# Bluetooth.net
KiCad netlist of a schematic drawn in Altium Designer
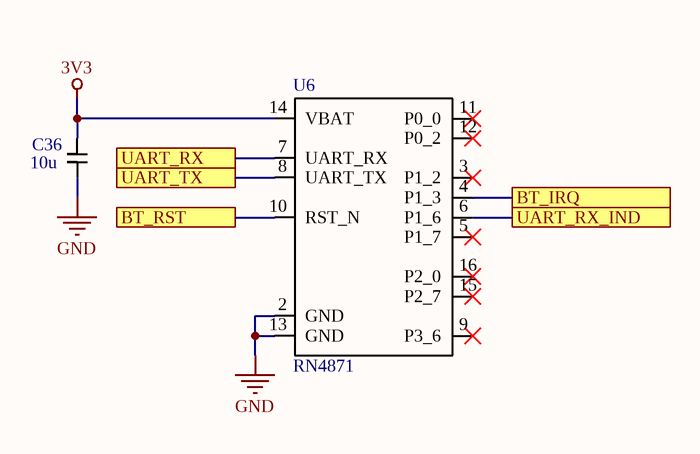
[diagram p0: Bluetooth.SchDoc]

(export (version "E")
  (design (tool "Eeschema 10.0.6"))
  (components
    (comp (ref "C36")
      (value "10u")
      (footprint "Capacitor_0603")
      (libsource (lib "NautilusKB") (part "Capacitor"))
    )
    (comp (ref "U6") (value "RN4871") (footprint "RN4871") (libsource (lib "NautilusKB") (part "RN4871")))
  )
  (nets
    (net (code "1") (name "/BT_IRQ") (class "Default")
      (node (ref "U6") (pin "4") (pinfunction "P1_3_4") (pintype "passive"))
    )
    (net (code "2") (name "/BT_RST") (class "Default")
      (node (ref "U6") (pin "10") (pinfunction "RST_N_10") (pintype "passive"))
    )
    (net (code "3") (name "/UART_RX") (class "Default")
      (node (ref "U6") (pin "7") (pinfunction "UART_RX_7") (pintype "passive"))
    )
    (net (code "4") (name "/UART_RX_IND") (class "Default")
      (node (ref "U6") (pin "6") (pinfunction "P1_6_6") (pintype "passive"))
    )
    (net (code "5") (name "/UART_TX") (class "Default")
      (node (ref "U6") (pin "8") (pinfunction "UART_TX_8") (pintype "passive"))
    )
    (net (code "6") (name "3V3") (class "Default")
      (node (ref "C36") (pin "2") (pintype "passive"))
      (node (ref "U6") (pin "14") (pinfunction "VBAT_14") (pintype "passive"))
    )
    (net (code "7") (name "GND") (class "Default")
      (node (ref "C36") (pin "1") (pintype "passive"))
      (node (ref "U6") (pin "13") (pinfunction "GND_13") (pintype "passive"))
      (node (ref "U6") (pin "2") (pinfunction "GND_2") (pintype "passive"))
    )
    (net (code "8") (name "unconnected-(U6-P0_0-Pad11)") (class "Default")
      (node (ref "U6") (pin "11") (pinfunction "P0_0_11") (pintype "passive+no_connect"))
    )
    (net (code "9") (name "unconnected-(U6-P0_2-Pad12)") (class "Default")
      (node (ref "U6") (pin "12") (pinfunction "P0_2_12") (pintype "passive+no_connect"))
    )
    (net (code "10") (name "unconnected-(U6-P1_2-Pad3)") (class "Default")
      (node (ref "U6") (pin "3") (pinfunction "P1_2_3") (pintype "passive+no_connect"))
    )
    (net (code "11") (name "unconnected-(U6-P1_7-Pad5)") (class "Default")
      (node (ref "U6") (pin "5") (pinfunction "P1_7_5") (pintype "passive+no_connect"))
    )
    (net (code "12") (name "unconnected-(U6-P2_0-Pad16)") (class "Default")
      (node (ref "U6") (pin "16") (pinfunction "P2_0_16") (pintype "passive+no_connect"))
    )
    (net (code "13") (name "unconnected-(U6-P2_7-Pad15)") (class "Default")
      (node (ref "U6") (pin "15") (pinfunction "P2_7_15") (pintype "passive+no_connect"))
    )
    (net (code "14") (name "unconnected-(U6-P3_6-Pad9)") (class "Default")
      (node (ref "U6") (pin "9") (pinfunction "P3_6_9") (pintype "passive+no_connect"))
    )
  )
)
